# HW_OPTO.net
KiCad netlist of a schematic drawn in Altium Designer
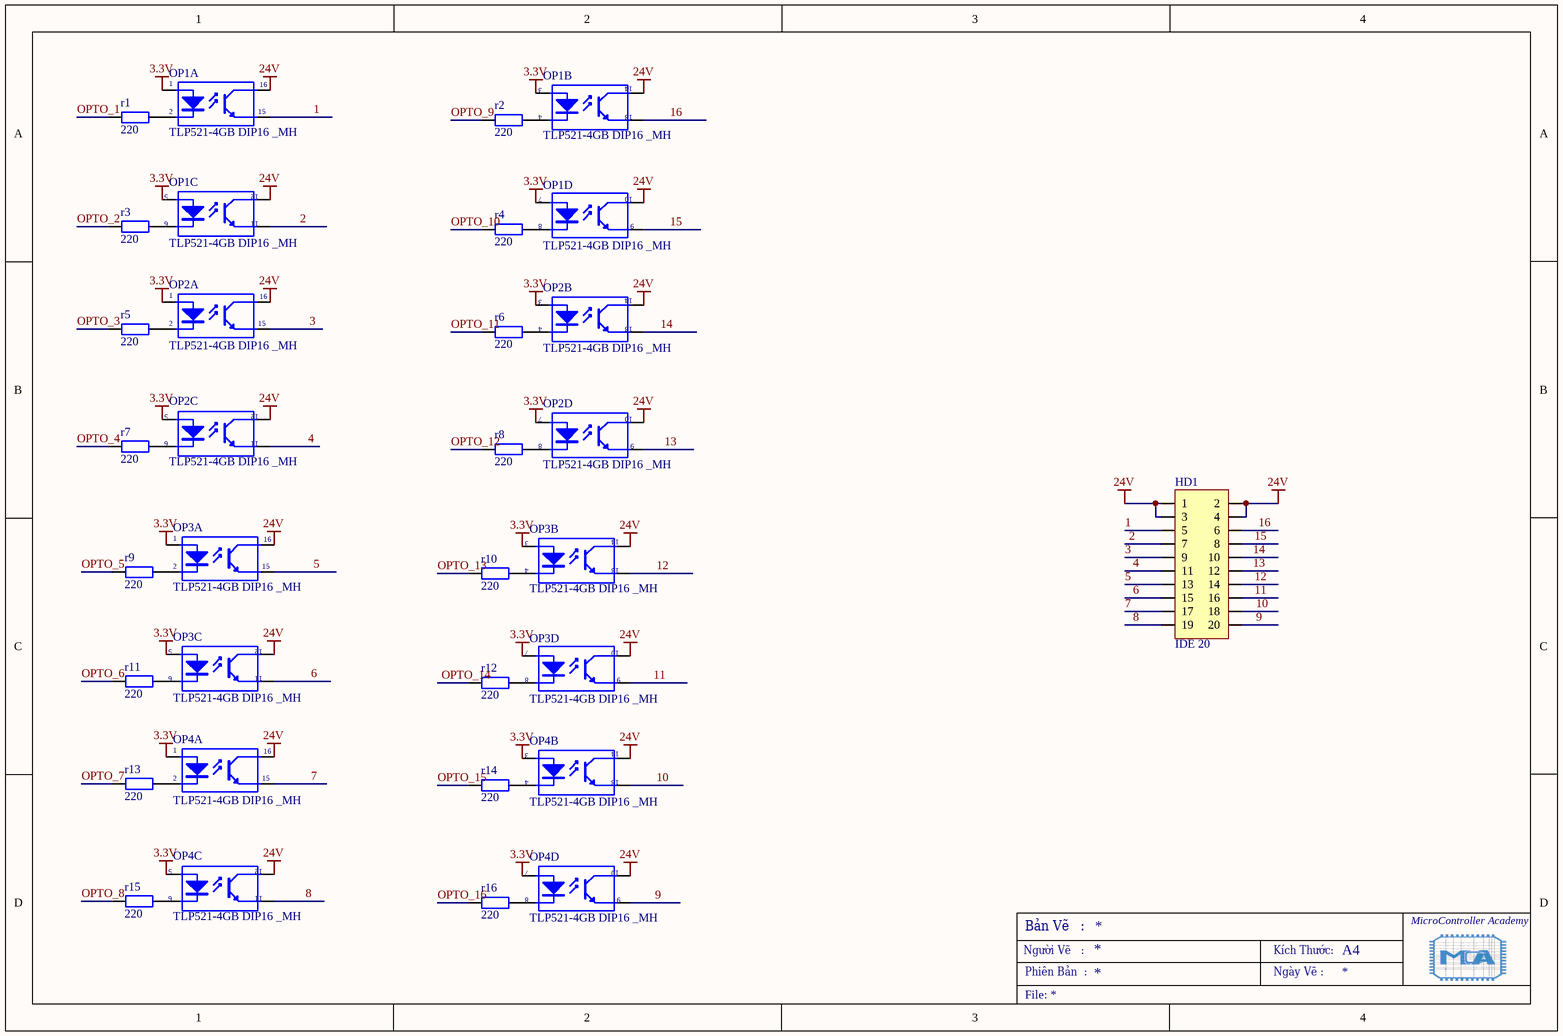
[diagram p0: HW_OPTO.SchDoc]

(export (version "E")
  (design (tool "Eeschema 10.0.6"))
  (components
    (comp (ref "HD1")
      (value "IDE 20")
      (footprint "CABLE 20")
      (description "IDE header 20P")
      (libsource (lib "MH_DA_THU_VIEN_ALTIUM_19112016") (part "IDE 20"))
    )
    (comp (ref "OP1")
      (value "TLP521-4GB DIP16 _MH")
      (footprint "DIP16")
      (libsource (lib "MH_DA_THU_VIEN_ALTIUM_19112016") (part "TLP521-4GB DIP16 _MH"))
    )
    (comp (ref "OP2")
      (value "TLP521-4GB DIP16 _MH")
      (footprint "DIP16")
      (libsource (lib "MH_DA_THU_VIEN_ALTIUM_19112016") (part "TLP521-4GB DIP16 _MH"))
    )
    (comp (ref "OP3")
      (value "TLP521-4GB DIP16 _MH")
      (footprint "DIP16")
      (libsource (lib "MH_DA_THU_VIEN_ALTIUM_19112016") (part "TLP521-4GB DIP16 _MH"))
    )
    (comp (ref "OP4")
      (value "TLP521-4GB DIP16 _MH")
      (footprint "DIP16")
      (libsource (lib "MH_DA_THU_VIEN_ALTIUM_19112016") (part "TLP521-4GB DIP16 _MH"))
    )
    (comp (ref "r1")
      (value "220")
      (footprint "Tro SMD 0805")
      (description "TRO_SMD_0805")
      (libsource (lib "MH_DA_THU_VIEN_ALTIUM_19112016") (part "TRO_SMD_0805_MH"))
    )
    (comp (ref "r2")
      (value "220")
      (footprint "Tro SMD 0805")
      (description "TRO_SMD_0805")
      (libsource (lib "MH_DA_THU_VIEN_ALTIUM_19112016") (part "TRO_SMD_0805_MH"))
    )
    (comp (ref "r3")
      (value "220")
      (footprint "Tro SMD 0805")
      (description "TRO_SMD_0805")
      (libsource (lib "MH_DA_THU_VIEN_ALTIUM_19112016") (part "TRO_SMD_0805_MH"))
    )
    (comp (ref "r4")
      (value "220")
      (footprint "Tro SMD 0805")
      (description "TRO_SMD_0805")
      (libsource (lib "MH_DA_THU_VIEN_ALTIUM_19112016") (part "TRO_SMD_0805_MH"))
    )
    (comp (ref "r5")
      (value "220")
      (footprint "Tro SMD 0805")
      (description "TRO_SMD_0805")
      (libsource (lib "MH_DA_THU_VIEN_ALTIUM_19112016") (part "TRO_SMD_0805_MH"))
    )
    (comp (ref "r6")
      (value "220")
      (footprint "Tro SMD 0805")
      (description "TRO_SMD_0805")
      (libsource (lib "MH_DA_THU_VIEN_ALTIUM_19112016") (part "TRO_SMD_0805_MH"))
    )
    (comp (ref "r7")
      (value "220")
      (footprint "Tro SMD 0805")
      (description "TRO_SMD_0805")
      (libsource (lib "MH_DA_THU_VIEN_ALTIUM_19112016") (part "TRO_SMD_0805_MH"))
    )
    (comp (ref "r8")
      (value "220")
      (footprint "Tro SMD 0805")
      (description "TRO_SMD_0805")
      (libsource (lib "MH_DA_THU_VIEN_ALTIUM_19112016") (part "TRO_SMD_0805_MH"))
    )
    (comp (ref "r9")
      (value "220")
      (footprint "Tro SMD 0805")
      (description "TRO_SMD_0805")
      (libsource (lib "MH_DA_THU_VIEN_ALTIUM_19112016") (part "TRO_SMD_0805_MH"))
    )
    (comp (ref "r10")
      (value "220")
      (footprint "Tro SMD 0805")
      (description "TRO_SMD_0805")
      (libsource (lib "MH_DA_THU_VIEN_ALTIUM_19112016") (part "TRO_SMD_0805_MH"))
    )
    (comp (ref "r11")
      (value "220")
      (footprint "Tro SMD 0805")
      (description "TRO_SMD_0805")
      (libsource (lib "MH_DA_THU_VIEN_ALTIUM_19112016") (part "TRO_SMD_0805_MH"))
    )
    (comp (ref "r12")
      (value "220")
      (footprint "Tro SMD 0805")
      (description "TRO_SMD_0805")
      (libsource (lib "MH_DA_THU_VIEN_ALTIUM_19112016") (part "TRO_SMD_0805_MH"))
    )
    (comp (ref "r13")
      (value "220")
      (footprint "Tro SMD 0805")
      (description "TRO_SMD_0805")
      (libsource (lib "MH_DA_THU_VIEN_ALTIUM_19112016") (part "TRO_SMD_0805_MH"))
    )
    (comp (ref "r14")
      (value "220")
      (footprint "Tro SMD 0805")
      (description "TRO_SMD_0805")
      (libsource (lib "MH_DA_THU_VIEN_ALTIUM_19112016") (part "TRO_SMD_0805_MH"))
    )
    (comp (ref "r15")
      (value "220")
      (footprint "Tro SMD 0805")
      (description "TRO_SMD_0805")
      (libsource (lib "MH_DA_THU_VIEN_ALTIUM_19112016") (part "TRO_SMD_0805_MH"))
    )
    (comp (ref "r16")
      (value "220")
      (footprint "Tro SMD 0805")
      (description "TRO_SMD_0805")
      (libsource (lib "MH_DA_THU_VIEN_ALTIUM_19112016") (part "TRO_SMD_0805_MH"))
    )
  )
  (nets
    (net (code "1") (name "/1") (class "Default")
      (node (ref "HD1") (pin "5") (pinfunction "5_5") (pintype "passive"))
      (node (ref "OP1") (pin "15") (pinfunction "E_15") (pintype "passive"))
    )
    (net (code "2") (name "/2") (class "Default")
      (node (ref "HD1") (pin "7") (pinfunction "7_7") (pintype "passive"))
      (node (ref "OP1") (pin "11") (pinfunction "E_11") (pintype "passive"))
    )
    (net (code "3") (name "/3") (class "Default")
      (node (ref "HD1") (pin "9") (pinfunction "9_9") (pintype "passive"))
      (node (ref "OP2") (pin "15") (pinfunction "E_15") (pintype "passive"))
    )
    (net (code "4") (name "/4") (class "Default")
      (node (ref "HD1") (pin "11") (pinfunction "11_11") (pintype "passive"))
      (node (ref "OP2") (pin "11") (pinfunction "E_11") (pintype "passive"))
    )
    (net (code "5") (name "/5") (class "Default")
      (node (ref "HD1") (pin "13") (pinfunction "13_13") (pintype "passive"))
      (node (ref "OP3") (pin "15") (pinfunction "E_15") (pintype "passive"))
    )
    (net (code "6") (name "/6") (class "Default")
      (node (ref "HD1") (pin "15") (pinfunction "15_15") (pintype "passive"))
      (node (ref "OP3") (pin "11") (pinfunction "E_11") (pintype "passive"))
    )
    (net (code "7") (name "/7") (class "Default")
      (node (ref "HD1") (pin "17") (pinfunction "17_17") (pintype "passive"))
      (node (ref "OP4") (pin "15") (pinfunction "E_15") (pintype "passive"))
    )
    (net (code "8") (name "/8") (class "Default")
      (node (ref "HD1") (pin "19") (pinfunction "19_19") (pintype "passive"))
      (node (ref "OP4") (pin "11") (pinfunction "E_11") (pintype "passive"))
    )
    (net (code "9") (name "/9") (class "Default")
      (node (ref "HD1") (pin "20") (pinfunction "20_20") (pintype "passive"))
      (node (ref "OP4") (pin "9") (pinfunction "E_9") (pintype "passive"))
    )
    (net (code "10") (name "/10") (class "Default")
      (node (ref "HD1") (pin "18") (pinfunction "18_18") (pintype "passive"))
      (node (ref "OP4") (pin "13") (pinfunction "E_13") (pintype "passive"))
    )
    (net (code "11") (name "/11") (class "Default")
      (node (ref "HD1") (pin "16") (pinfunction "16_16") (pintype "passive"))
      (node (ref "OP3") (pin "9") (pinfunction "E_9") (pintype "passive"))
    )
    (net (code "12") (name "/12") (class "Default")
      (node (ref "HD1") (pin "14") (pinfunction "14_14") (pintype "passive"))
      (node (ref "OP3") (pin "13") (pinfunction "E_13") (pintype "passive"))
    )
    (net (code "13") (name "/13") (class "Default")
      (node (ref "HD1") (pin "12") (pinfunction "12_12") (pintype "passive"))
      (node (ref "OP2") (pin "9") (pinfunction "E_9") (pintype "passive"))
    )
    (net (code "14") (name "/14") (class "Default")
      (node (ref "HD1") (pin "10") (pinfunction "10_10") (pintype "passive"))
      (node (ref "OP2") (pin "13") (pinfunction "E_13") (pintype "passive"))
    )
    (net (code "15") (name "/15") (class "Default")
      (node (ref "HD1") (pin "8") (pinfunction "8_8") (pintype "passive"))
      (node (ref "OP1") (pin "9") (pinfunction "E_9") (pintype "passive"))
    )
    (net (code "16") (name "/16") (class "Default")
      (node (ref "HD1") (pin "6") (pinfunction "6_6") (pintype "passive"))
      (node (ref "OP1") (pin "13") (pinfunction "E_13") (pintype "passive"))
    )
    (net (code "17") (name "/OPTO_1") (class "Default")
      (node (ref "r1") (pin "1") (pinfunction "1_1") (pintype "passive"))
    )
    (net (code "18") (name "/OPTO_2") (class "Default")
      (node (ref "r3") (pin "1") (pinfunction "1_1") (pintype "passive"))
    )
    (net (code "19") (name "/OPTO_3") (class "Default")
      (node (ref "r5") (pin "1") (pinfunction "1_1") (pintype "passive"))
    )
    (net (code "20") (name "/OPTO_4") (class "Default")
      (node (ref "r7") (pin "1") (pinfunction "1_1") (pintype "passive"))
    )
    (net (code "21") (name "/OPTO_5") (class "Default")
      (node (ref "r9") (pin "1") (pinfunction "1_1") (pintype "passive"))
    )
    (net (code "22") (name "/OPTO_6") (class "Default")
      (node (ref "r11") (pin "1") (pinfunction "1_1") (pintype "passive"))
    )
    (net (code "23") (name "/OPTO_7") (class "Default")
      (node (ref "r13") (pin "1") (pinfunction "1_1") (pintype "passive"))
    )
    (net (code "24") (name "/OPTO_8") (class "Default")
      (node (ref "r15") (pin "1") (pinfunction "1_1") (pintype "passive"))
    )
    (net (code "25") (name "/OPTO_9") (class "Default")
      (node (ref "r2") (pin "1") (pinfunction "1_1") (pintype "passive"))
    )
    (net (code "26") (name "/OPTO_10") (class "Default")
      (node (ref "r4") (pin "1") (pinfunction "1_1") (pintype "passive"))
    )
    (net (code "27") (name "/OPTO_11") (class "Default")
      (node (ref "r6") (pin "1") (pinfunction "1_1") (pintype "passive"))
    )
    (net (code "28") (name "/OPTO_12") (class "Default")
      (node (ref "r8") (pin "1") (pinfunction "1_1") (pintype "passive"))
    )
    (net (code "29") (name "/OPTO_13") (class "Default")
      (node (ref "r10") (pin "1") (pinfunction "1_1") (pintype "passive"))
    )
    (net (code "30") (name "/OPTO_14") (class "Default")
      (node (ref "r12") (pin "1") (pinfunction "1_1") (pintype "passive"))
    )
    (net (code "31") (name "/OPTO_15") (class "Default")
      (node (ref "r14") (pin "1") (pinfunction "1_1") (pintype "passive"))
    )
    (net (code "32") (name "/OPTO_16") (class "Default")
      (node (ref "r16") (pin "1") (pinfunction "1_1") (pintype "passive"))
    )
    (net (code "33") (name "3.3V") (class "Default")
      (node (ref "OP1") (pin "1") (pinfunction "A_1") (pintype "passive"))
      (node (ref "OP1") (pin "3") (pinfunction "A_3") (pintype "passive"))
      (node (ref "OP1") (pin "5") (pinfunction "A_5") (pintype "passive"))
      (node (ref "OP1") (pin "7") (pinfunction "A_7") (pintype "passive"))
      (node (ref "OP2") (pin "1") (pinfunction "A_1") (pintype "passive"))
      (node (ref "OP2") (pin "3") (pinfunction "A_3") (pintype "passive"))
      (node (ref "OP2") (pin "5") (pinfunction "A_5") (pintype "passive"))
      (node (ref "OP2") (pin "7") (pinfunction "A_7") (pintype "passive"))
      (node (ref "OP3") (pin "1") (pinfunction "A_1") (pintype "passive"))
      (node (ref "OP3") (pin "3") (pinfunction "A_3") (pintype "passive"))
      (node (ref "OP3") (pin "5") (pinfunction "A_5") (pintype "passive"))
      (node (ref "OP3") (pin "7") (pinfunction "A_7") (pintype "passive"))
      (node (ref "OP4") (pin "1") (pinfunction "A_1") (pintype "passive"))
      (node (ref "OP4") (pin "3") (pinfunction "A_3") (pintype "passive"))
      (node (ref "OP4") (pin "5") (pinfunction "A_5") (pintype "passive"))
      (node (ref "OP4") (pin "7") (pinfunction "A_7") (pintype "passive"))
    )
    (net (code "34") (name "24V") (class "Default")
      (node (ref "HD1") (pin "1") (pinfunction "1_1") (pintype "passive"))
      (node (ref "HD1") (pin "2") (pinfunction "2_2") (pintype "passive"))
      (node (ref "HD1") (pin "3") (pinfunction "3_3") (pintype "passive"))
      (node (ref "HD1") (pin "4") (pinfunction "4_4") (pintype "passive"))
      (node (ref "OP1") (pin "10") (pinfunction "C_10") (pintype "passive"))
      (node (ref "OP1") (pin "12") (pinfunction "C_12") (pintype "passive"))
      (node (ref "OP1") (pin "14") (pinfunction "C_14") (pintype "passive"))
      (node (ref "OP1") (pin "16") (pinfunction "C_16") (pintype "passive"))
      (node (ref "OP2") (pin "10") (pinfunction "C_10") (pintype "passive"))
      (node (ref "OP2") (pin "12") (pinfunction "C_12") (pintype "passive"))
      (node (ref "OP2") (pin "14") (pinfunction "C_14") (pintype "passive"))
      (node (ref "OP2") (pin "16") (pinfunction "C_16") (pintype "passive"))
      (node (ref "OP3") (pin "10") (pinfunction "C_10") (pintype "passive"))
      (node (ref "OP3") (pin "12") (pinfunction "C_12") (pintype "passive"))
      (node (ref "OP3") (pin "14") (pinfunction "C_14") (pintype "passive"))
      (node (ref "OP3") (pin "16") (pinfunction "C_16") (pintype "passive"))
      (node (ref "OP4") (pin "10") (pinfunction "C_10") (pintype "passive"))
      (node (ref "OP4") (pin "12") (pinfunction "C_12") (pintype "passive"))
      (node (ref "OP4") (pin "14") (pinfunction "C_14") (pintype "passive"))
      (node (ref "OP4") (pin "16") (pinfunction "C_16") (pintype "passive"))
    )
    (net (code "35") (name "Net-(OP1A-K)") (class "Default")
      (node (ref "OP1") (pin "2") (pinfunction "K_2") (pintype "passive"))
      (node (ref "r1") (pin "2") (pinfunction "2_2") (pintype "passive"))
    )
    (net (code "36") (name "Net-(OP1B-K)") (class "Default")
      (node (ref "OP1") (pin "4") (pinfunction "K_4") (pintype "passive"))
      (node (ref "r2") (pin "2") (pinfunction "2_2") (pintype "passive"))
    )
    (net (code "37") (name "Net-(OP1C-K)") (class "Default")
      (node (ref "OP1") (pin "6") (pinfunction "K_6") (pintype "passive"))
      (node (ref "r3") (pin "2") (pinfunction "2_2") (pintype "passive"))
    )
    (net (code "38") (name "Net-(OP1D-K)") (class "Default")
      (node (ref "OP1") (pin "8") (pinfunction "K_8") (pintype "passive"))
      (node (ref "r4") (pin "2") (pinfunction "2_2") (pintype "passive"))
    )
    (net (code "39") (name "Net-(OP2A-K)") (class "Default")
      (node (ref "OP2") (pin "2") (pinfunction "K_2") (pintype "passive"))
      (node (ref "r5") (pin "2") (pinfunction "2_2") (pintype "passive"))
    )
    (net (code "40") (name "Net-(OP2B-K)") (class "Default")
      (node (ref "OP2") (pin "4") (pinfunction "K_4") (pintype "passive"))
      (node (ref "r6") (pin "2") (pinfunction "2_2") (pintype "passive"))
    )
    (net (code "41") (name "Net-(OP2C-K)") (class "Default")
      (node (ref "OP2") (pin "6") (pinfunction "K_6") (pintype "passive"))
      (node (ref "r7") (pin "2") (pinfunction "2_2") (pintype "passive"))
    )
    (net (code "42") (name "Net-(OP2D-K)") (class "Default")
      (node (ref "OP2") (pin "8") (pinfunction "K_8") (pintype "passive"))
      (node (ref "r8") (pin "2") (pinfunction "2_2") (pintype "passive"))
    )
    (net (code "43") (name "Net-(OP3A-K)") (class "Default")
      (node (ref "OP3") (pin "2") (pinfunction "K_2") (pintype "passive"))
      (node (ref "r9") (pin "2") (pinfunction "2_2") (pintype "passive"))
    )
    (net (code "44") (name "Net-(OP3B-K)") (class "Default")
      (node (ref "OP3") (pin "4") (pinfunction "K_4") (pintype "passive"))
      (node (ref "r10") (pin "2") (pinfunction "2_2") (pintype "passive"))
    )
    (net (code "45") (name "Net-(OP3C-K)") (class "Default")
      (node (ref "OP3") (pin "6") (pinfunction "K_6") (pintype "passive"))
      (node (ref "r11") (pin "2") (pinfunction "2_2") (pintype "passive"))
    )
    (net (code "46") (name "Net-(OP3D-K)") (class "Default")
      (node (ref "OP3") (pin "8") (pinfunction "K_8") (pintype "passive"))
      (node (ref "r12") (pin "2") (pinfunction "2_2") (pintype "passive"))
    )
    (net (code "47") (name "Net-(OP4A-K)") (class "Default")
      (node (ref "OP4") (pin "2") (pinfunction "K_2") (pintype "passive"))
      (node (ref "r13") (pin "2") (pinfunction "2_2") (pintype "passive"))
    )
    (net (code "48") (name "Net-(OP4B-K)") (class "Default")
      (node (ref "OP4") (pin "4") (pinfunction "K_4") (pintype "passive"))
      (node (ref "r14") (pin "2") (pinfunction "2_2") (pintype "passive"))
    )
    (net (code "49") (name "Net-(OP4C-K)") (class "Default")
      (node (ref "OP4") (pin "6") (pinfunction "K_6") (pintype "passive"))
      (node (ref "r15") (pin "2") (pinfunction "2_2") (pintype "passive"))
    )
    (net (code "50") (name "Net-(OP4D-K)") (class "Default")
      (node (ref "OP4") (pin "8") (pinfunction "K_8") (pintype "passive"))
      (node (ref "r16") (pin "2") (pinfunction "2_2") (pintype "passive"))
    )
  )
)
